# Shema.net
KiCad netlist of a schematic drawn in Altium Designer
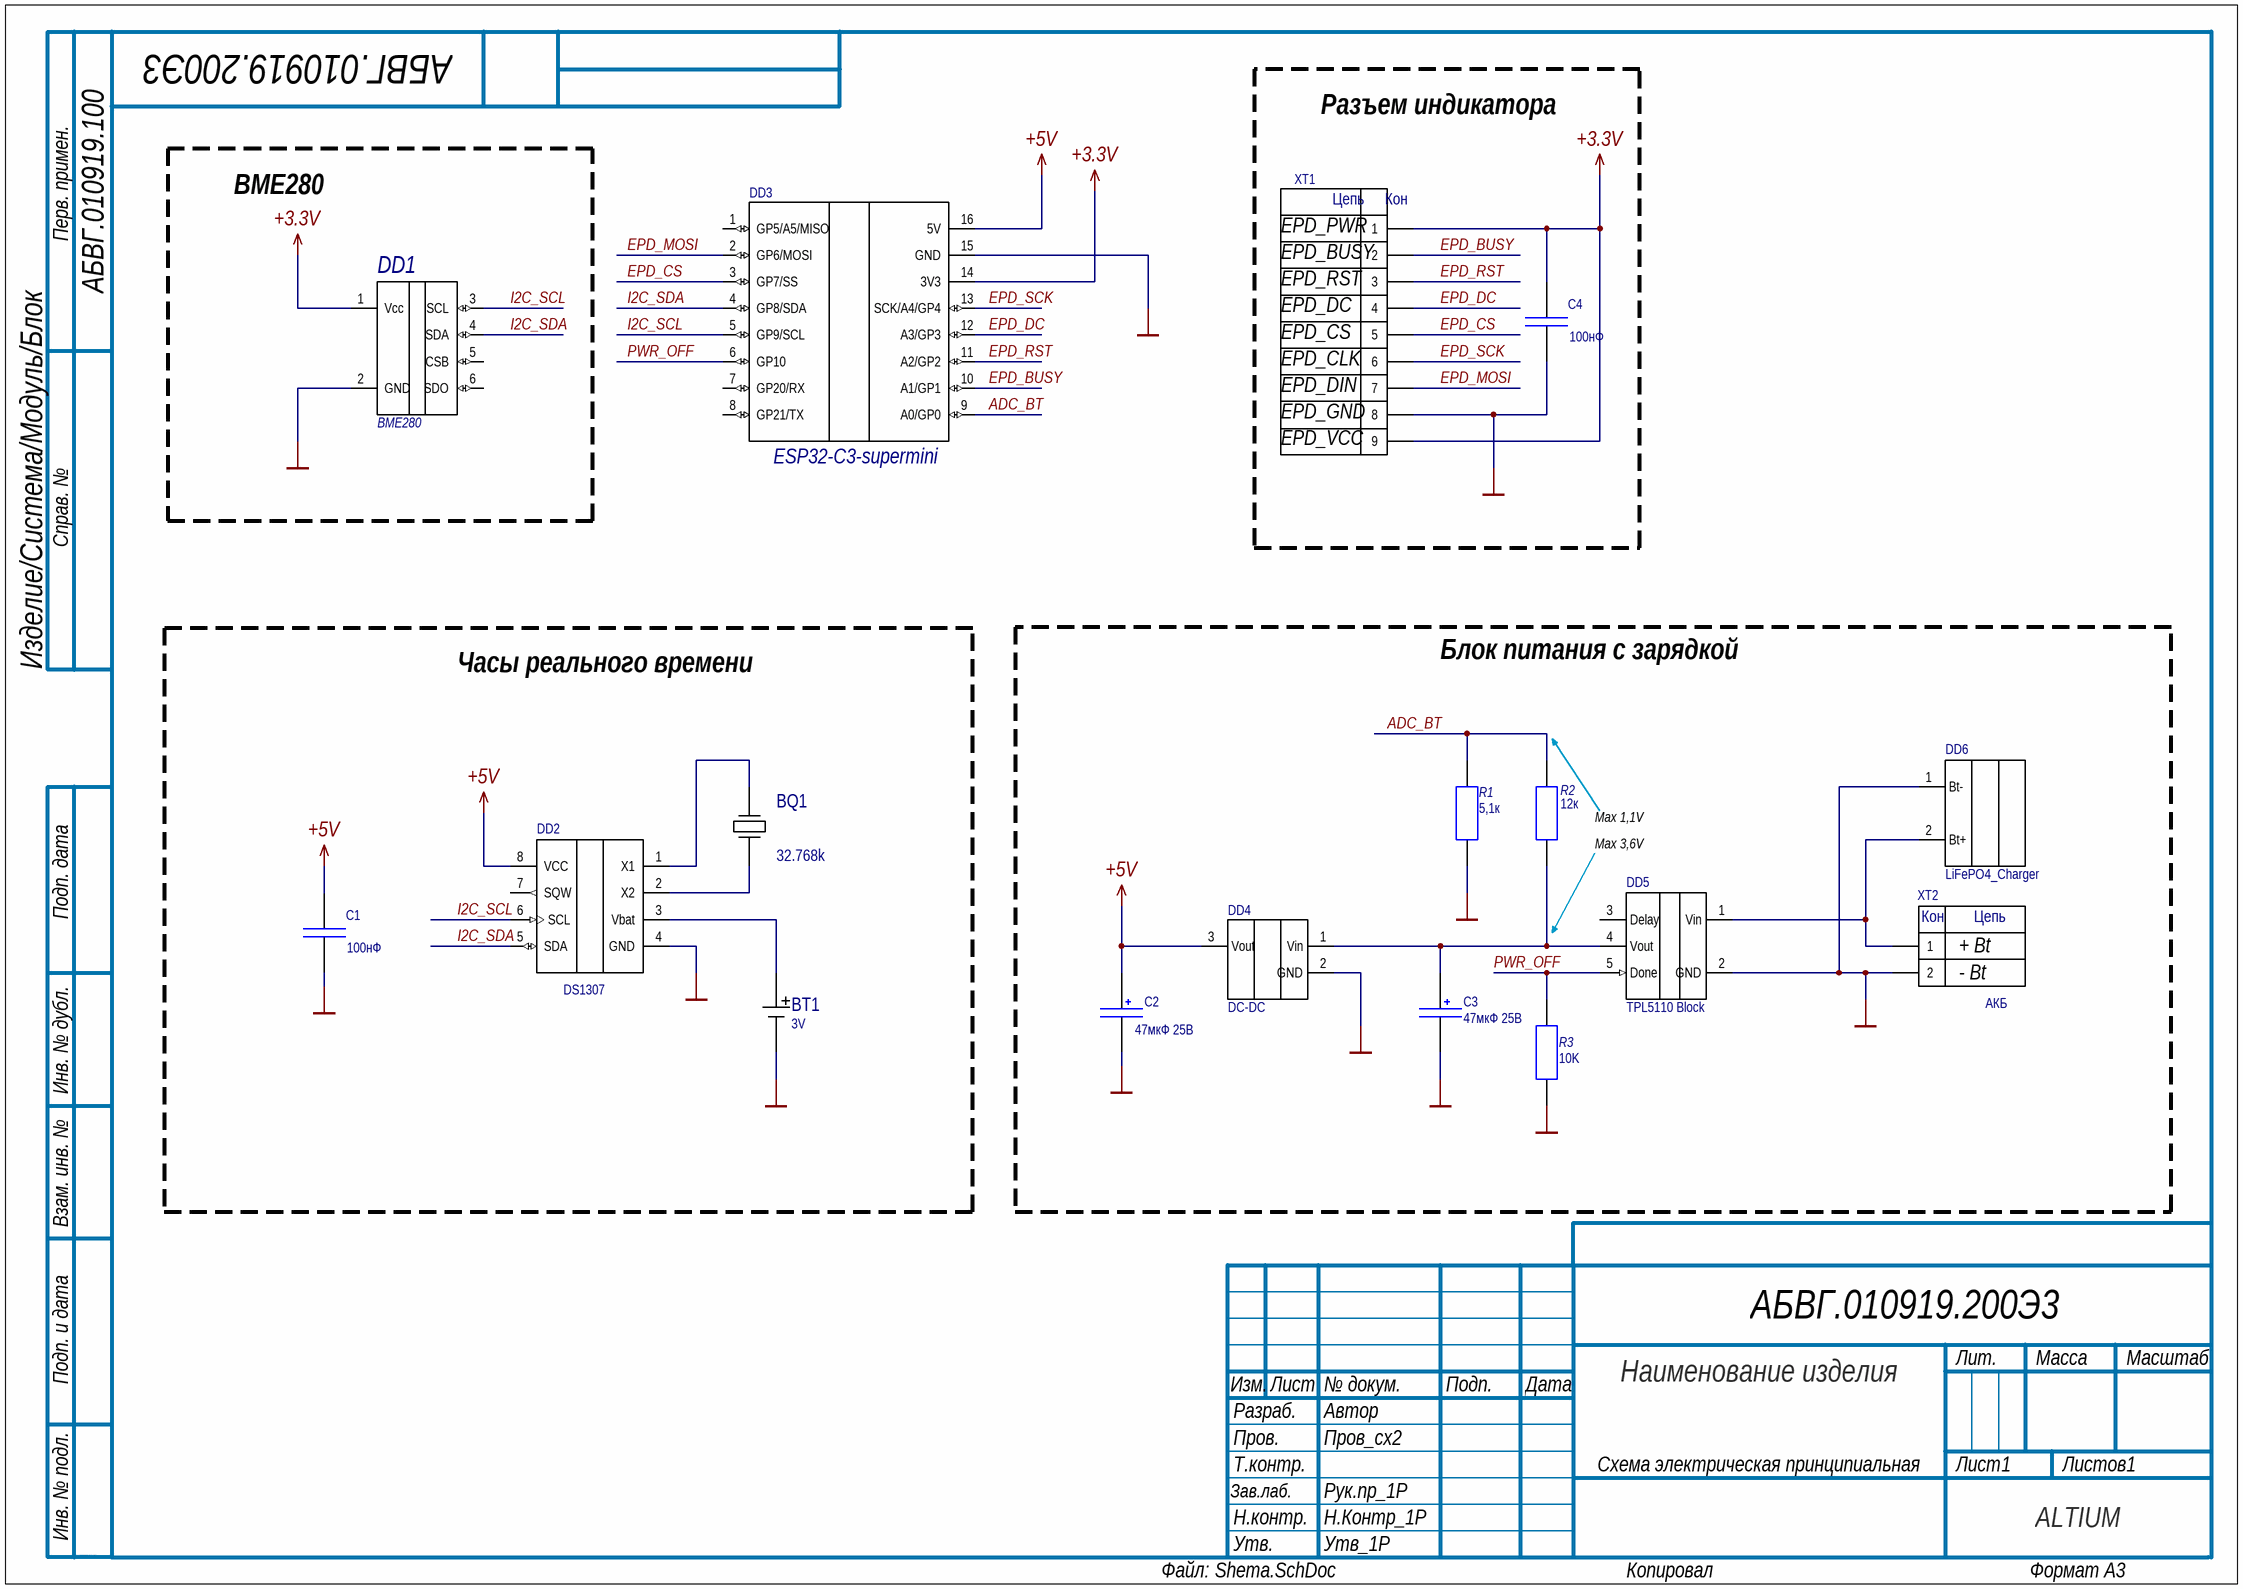
[diagram p0: Shema.SchDoc]

(export (version "E")
  (design (tool "Eeschema 10.0.6"))
  (components
    (comp (ref "BQ1")
      (value "32.768k")
      (footprint "XTAL_2x6_SMD")
      (description "Кварцевый резонатор 32768 Гц (часовой)")
      (fields (field (name "MANUFACTURER") "Китай"))
      (libsource (lib "MyDataBase_Libs") (part "XTAL"))
    )
    (comp (ref "BT1")
      (value "3V")
      (footprint "CR1220")
      (description "Держатель батарейки CR1220")
      (fields (field (name "MANUFACTURER") "Китай") (field (name "Comment") "CR1220"))
      (libsource (lib "MyDataBase_Libs") (part "BatteryHolder"))
    )
    (comp (ref "C1")
      (value "100нФ")
      (footprint "Cap_0805")
      (description "Конденсатор")
      (fields (field (name "Comment") "Capacitor"))
      (libsource (lib "Alex_Lib") (part "Capacitor"))
    )
    (comp (ref "C2")
      (value "47мкФ 25В")
      (footprint "Tantal 2917_7343")
      (description "Конденсатор эл-лит")
      (fields (field (name "Comment") "Capacitor_Polar"))
      (libsource (lib "Alex_Lib") (part "Capacitor_Polar"))
    )
    (comp (ref "C3")
      (value "47мкФ 25В")
      (footprint "Tantal 2917_7343")
      (description "Конденсатор эл-лит")
      (fields (field (name "Comment") "Capacitor_Polar"))
      (libsource (lib "Alex_Lib") (part "Capacitor_Polar"))
    )
    (comp (ref "C4")
      (value "100нФ")
      (footprint "Cap_0805")
      (description "Конденсатор")
      (fields (field (name "Comment") "Capacitor"))
      (libsource (lib "Alex_Lib") (part "Capacitor"))
    )
    (comp (ref "DD1")
      (value "Обозначение при заказе")
      (footprint "BME280_6Pin_1")
      (description "Описание свойств компонента")
      (fields (field (name "NAME") "BME280"))
      (libsource (lib "Alex_Lib") (part "BME280_6Pin"))
    )
    (comp (ref "DD2")
      (value "DS1307")
      (footprint "8S1_M")
      (description "Serial Clock")
      (fields (field (name "NAME") "DS1307"))
      (libsource (lib "Alex_Lib") (part "DS1307"))
    )
    (comp (ref "DD3")
      (value "ESP32-C3-supermini")
      (footprint "ESP32-C3 supermini_SMD")
      (description "esp32-c3-supermini")
      (fields (field (name "Comment") "ESP32-c3-supermini"))
      (libsource (lib "Alex_Lib") (part "ESP32-c3-supermini"))
    )
    (comp (ref "DD4")
      (value "DC-DC_0.9-5V")
      (footprint "DC-DC_0.9-5V")
      (description "DC-DC Converter")
      (fields (field (name "NAME") "DC-DC"))
      (libsource (lib "Alex_Lib") (part "DC-DC_0.9-5V"))
    )
    (comp (ref "DD5")
      (value "TPL5110 Module")
      (footprint "TPL5110 Module")
      (description "DC-DC Converter")
      (fields (field (name "NAME") "TPL5110 Block"))
      (libsource (lib "Alex_Lib") (part "TPL5110 Module"))
    )
    (comp (ref "DD6")
      (value "LiFePO4_Charger")
      (footprint "LiFePO4_Charger")
      (description "DC-DC Converter")
      (fields (field (name "NAME") "LiFePO4_Charger"))
      (libsource (lib "Alex_Lib") (part "LiFePO4_Charger"))
    )
    (comp (ref "R1")
      (value "5,1к")
      (footprint "Res_0805")
      (description "Резистор")
      (fields (field (name "Comment") "Resistor"))
      (libsource (lib "Alex_Lib") (part "Resistor"))
    )
    (comp (ref "R2")
      (value "12к")
      (footprint "Res_0805")
      (description "Резистор")
      (fields (field (name "Comment") "Resistor"))
      (libsource (lib "Alex_Lib") (part "Resistor"))
    )
    (comp (ref "R3")
      (value "10K")
      (footprint "Res_0805")
      (description "Резистор")
      (fields (field (name "Comment") "Resistor"))
      (libsource (lib "Alex_Lib") (part "Resistor"))
    )
    (comp (ref "XT1")
      (value "Header 1X9")
      (footprint "PLS-9R-U1")
      (libsource (lib "Alex_Lib") (part "Header 1X9"))
    )
    (comp (ref "XT2")
      (value "АКБ")
      (footprint "PIN_1X2_5.08_DIP")
      (description "Header 1x3")
      (fields (field (name "Comment") "Header 1x2"))
      (libsource (lib "Alex_Lib") (part "Header 1x2"))
    )
  )
  (nets
    (net (code "1") (name "+3.3V") (class "Default")
      (node (ref "C4") (pin "2") (pinfunction "2_2") (pintype "passive"))
      (node (ref "DD1") (pin "1") (pinfunction "Vcc_1") (pintype "power_in"))
      (node (ref "DD3") (pin "14") (pinfunction "3V3_14") (pintype "power_in"))
      (node (ref "XT1") (pin "1") (pinfunction "1_1") (pintype "passive"))
      (node (ref "XT1") (pin "9") (pinfunction "9_9") (pintype "passive"))
    )
    (net (code "2") (name "+5V") (class "Default")
      (node (ref "C1") (pin "2") (pinfunction "2_2") (pintype "passive"))
      (node (ref "C2") (pin "1") (pinfunction "1_1") (pintype "passive"))
      (node (ref "DD2") (pin "8") (pinfunction "VCC_8") (pintype "power_in"))
      (node (ref "DD3") (pin "16") (pinfunction "5V_16") (pintype "power_in"))
      (node (ref "DD4") (pin "3") (pinfunction "Vout_3") (pintype "power_in"))
    )
    (net (code "3") (name "/ADC_BT") (class "Default")
      (node (ref "DD3") (pin "9") (pinfunction "A0/GP0_9") (pintype "bidirectional"))
      (node (ref "R1") (pin "1") (pinfunction "1_1") (pintype "passive"))
      (node (ref "R2") (pin "2") (pinfunction "2_2") (pintype "passive"))
    )
    (net (code "4") (name "/EPD_BUSY") (class "Default")
      (node (ref "DD3") (pin "10") (pinfunction "A1/GP1_10") (pintype "bidirectional"))
      (node (ref "XT1") (pin "2") (pinfunction "2_2") (pintype "passive"))
    )
    (net (code "5") (name "/EPD_CS") (class "Default")
      (node (ref "DD3") (pin "3") (pinfunction "GP7/SS_3") (pintype "bidirectional"))
      (node (ref "XT1") (pin "5") (pinfunction "5_5") (pintype "passive"))
    )
    (net (code "6") (name "/EPD_DC") (class "Default")
      (node (ref "DD3") (pin "12") (pinfunction "A3/GP3_12") (pintype "bidirectional"))
      (node (ref "XT1") (pin "4") (pinfunction "4_4") (pintype "passive"))
    )
    (net (code "7") (name "/EPD_MOSI") (class "Default")
      (node (ref "DD3") (pin "2") (pinfunction "GP6/MOSI_2") (pintype "bidirectional"))
      (node (ref "XT1") (pin "7") (pinfunction "7_7") (pintype "passive"))
    )
    (net (code "8") (name "/EPD_RST") (class "Default")
      (node (ref "DD3") (pin "11") (pinfunction "A2/GP2_11") (pintype "bidirectional"))
      (node (ref "XT1") (pin "3") (pinfunction "3_3") (pintype "passive"))
    )
    (net (code "9") (name "/EPD_SCK") (class "Default")
      (node (ref "DD3") (pin "13") (pinfunction "SCK/A4/GP4_13") (pintype "bidirectional"))
      (node (ref "XT1") (pin "6") (pinfunction "6_6") (pintype "passive"))
    )
    (net (code "10") (name "/I2C_SCL") (class "Default")
      (node (ref "DD1") (pin "3") (pinfunction "SCL_3") (pintype "bidirectional"))
      (node (ref "DD2") (pin "6") (pinfunction "SCL_6") (pintype "input"))
      (node (ref "DD3") (pin "5") (pinfunction "GP9/SCL_5") (pintype "bidirectional"))
    )
    (net (code "11") (name "/I2C_SDA") (class "Default")
      (node (ref "DD1") (pin "4") (pinfunction "SDA_4") (pintype "bidirectional"))
      (node (ref "DD2") (pin "5") (pinfunction "SDA_5") (pintype "bidirectional"))
      (node (ref "DD3") (pin "4") (pinfunction "GP8/SDA_4") (pintype "bidirectional"))
    )
    (net (code "12") (name "/PWR_OFF") (class "Default")
      (node (ref "DD3") (pin "6") (pinfunction "GP10_6") (pintype "bidirectional"))
      (node (ref "DD5") (pin "5") (pinfunction "Done_5") (pintype "input"))
      (node (ref "R3") (pin "2") (pinfunction "2_2") (pintype "passive"))
    )
    (net (code "13") (name "GND") (class "Default")
      (node (ref "BT1") (pin "2") (pinfunction "-_2") (pintype "passive"))
      (node (ref "C1") (pin "1") (pinfunction "1_1") (pintype "passive"))
      (node (ref "C2") (pin "2") (pinfunction "2_2") (pintype "passive"))
      (node (ref "C3") (pin "2") (pinfunction "2_2") (pintype "passive"))
      (node (ref "C4") (pin "1") (pinfunction "1_1") (pintype "passive"))
      (node (ref "DD1") (pin "2") (pinfunction "GND_2") (pintype "power_in"))
      (node (ref "DD2") (pin "4") (pinfunction "GND_4") (pintype "power_in"))
      (node (ref "DD3") (pin "15") (pinfunction "GND_15") (pintype "power_in"))
      (node (ref "DD4") (pin "2") (pinfunction "GND_2") (pintype "power_in"))
      (node (ref "DD5") (pin "2") (pinfunction "GND_2") (pintype "power_in"))
      (node (ref "DD6") (pin "1") (pinfunction "Bt-_1") (pintype "power_in"))
      (node (ref "R1") (pin "2") (pinfunction "2_2") (pintype "passive"))
      (node (ref "R3") (pin "1") (pinfunction "1_1") (pintype "passive"))
      (node (ref "XT1") (pin "8") (pinfunction "8_8") (pintype "passive"))
      (node (ref "XT2") (pin "2") (pinfunction "2_2") (pintype "passive"))
    )
    (net (code "14") (name "Net-(BQ1-OSC1)") (class "Default")
      (node (ref "BQ1") (pin "1") (pinfunction "OSC1_1") (pintype "passive"))
      (node (ref "DD2") (pin "2") (pinfunction "X2_2") (pintype "passive"))
    )
    (net (code "15") (name "Net-(BQ1-OSC2)") (class "Default")
      (node (ref "BQ1") (pin "2") (pinfunction "OSC2_2") (pintype "passive"))
      (node (ref "DD2") (pin "1") (pinfunction "X1_1") (pintype "passive"))
    )
    (net (code "16") (name "Net-(BT1-+)") (class "Default")
      (node (ref "BT1") (pin "1") (pinfunction "+_1") (pintype "passive"))
      (node (ref "DD2") (pin "3") (pinfunction "Vbat_3") (pintype "power_in"))
    )
    (net (code "17") (name "Net-(DD4-Vin)") (class "Default")
      (node (ref "C3") (pin "1") (pinfunction "1_1") (pintype "passive"))
      (node (ref "DD4") (pin "1") (pinfunction "Vin_1") (pintype "power_in"))
      (node (ref "DD5") (pin "4") (pinfunction "Vout_4") (pintype "power_in"))
      (node (ref "R2") (pin "1") (pinfunction "1_1") (pintype "passive"))
    )
    (net (code "18") (name "Net-(DD5-Vin)") (class "Default")
      (node (ref "DD5") (pin "1") (pinfunction "Vin_1") (pintype "power_in"))
      (node (ref "DD6") (pin "2") (pinfunction "Bt+_2") (pintype "power_in"))
      (node (ref "XT2") (pin "1") (pinfunction "1_1") (pintype "passive"))
    )
    (net (code "19") (name "unconnected-(DD1-CSB-Pad5)") (class "Default")
      (node (ref "DD1") (pin "5") (pinfunction "CSB_5") (pintype "bidirectional"))
    )
    (net (code "20") (name "unconnected-(DD1-SDO-Pad6)") (class "Default")
      (node (ref "DD1") (pin "6") (pinfunction "SDO_6") (pintype "bidirectional"))
    )
    (net (code "21") (name "unconnected-(DD2-SQW-Pad7)") (class "Default")
      (node (ref "DD2") (pin "7") (pinfunction "SQW_7") (pintype "output"))
    )
    (net (code "22") (name "unconnected-(DD3-GP5{slash}A5{slash}MISO-Pad1)") (class "Default")
      (node (ref "DD3") (pin "1") (pinfunction "GP5/A5/MISO_1") (pintype "bidirectional"))
    )
    (net (code "23") (name "unconnected-(DD3-GP20{slash}RX-Pad7)") (class "Default")
      (node (ref "DD3") (pin "7") (pinfunction "GP20/RX_7") (pintype "bidirectional"))
    )
    (net (code "24") (name "unconnected-(DD3-GP21{slash}TX-Pad8)") (class "Default")
      (node (ref "DD3") (pin "8") (pinfunction "GP21/TX_8") (pintype "bidirectional"))
    )
    (net (code "25") (name "unconnected-(DD5-Delay-Pad3)") (class "Default")
      (node (ref "DD5") (pin "3") (pinfunction "Delay_3") (pintype "passive"))
    )
  )
)
